# Soil_Moisture_V1_0.net
KiCad netlist of a schematic drawn in EAGLE
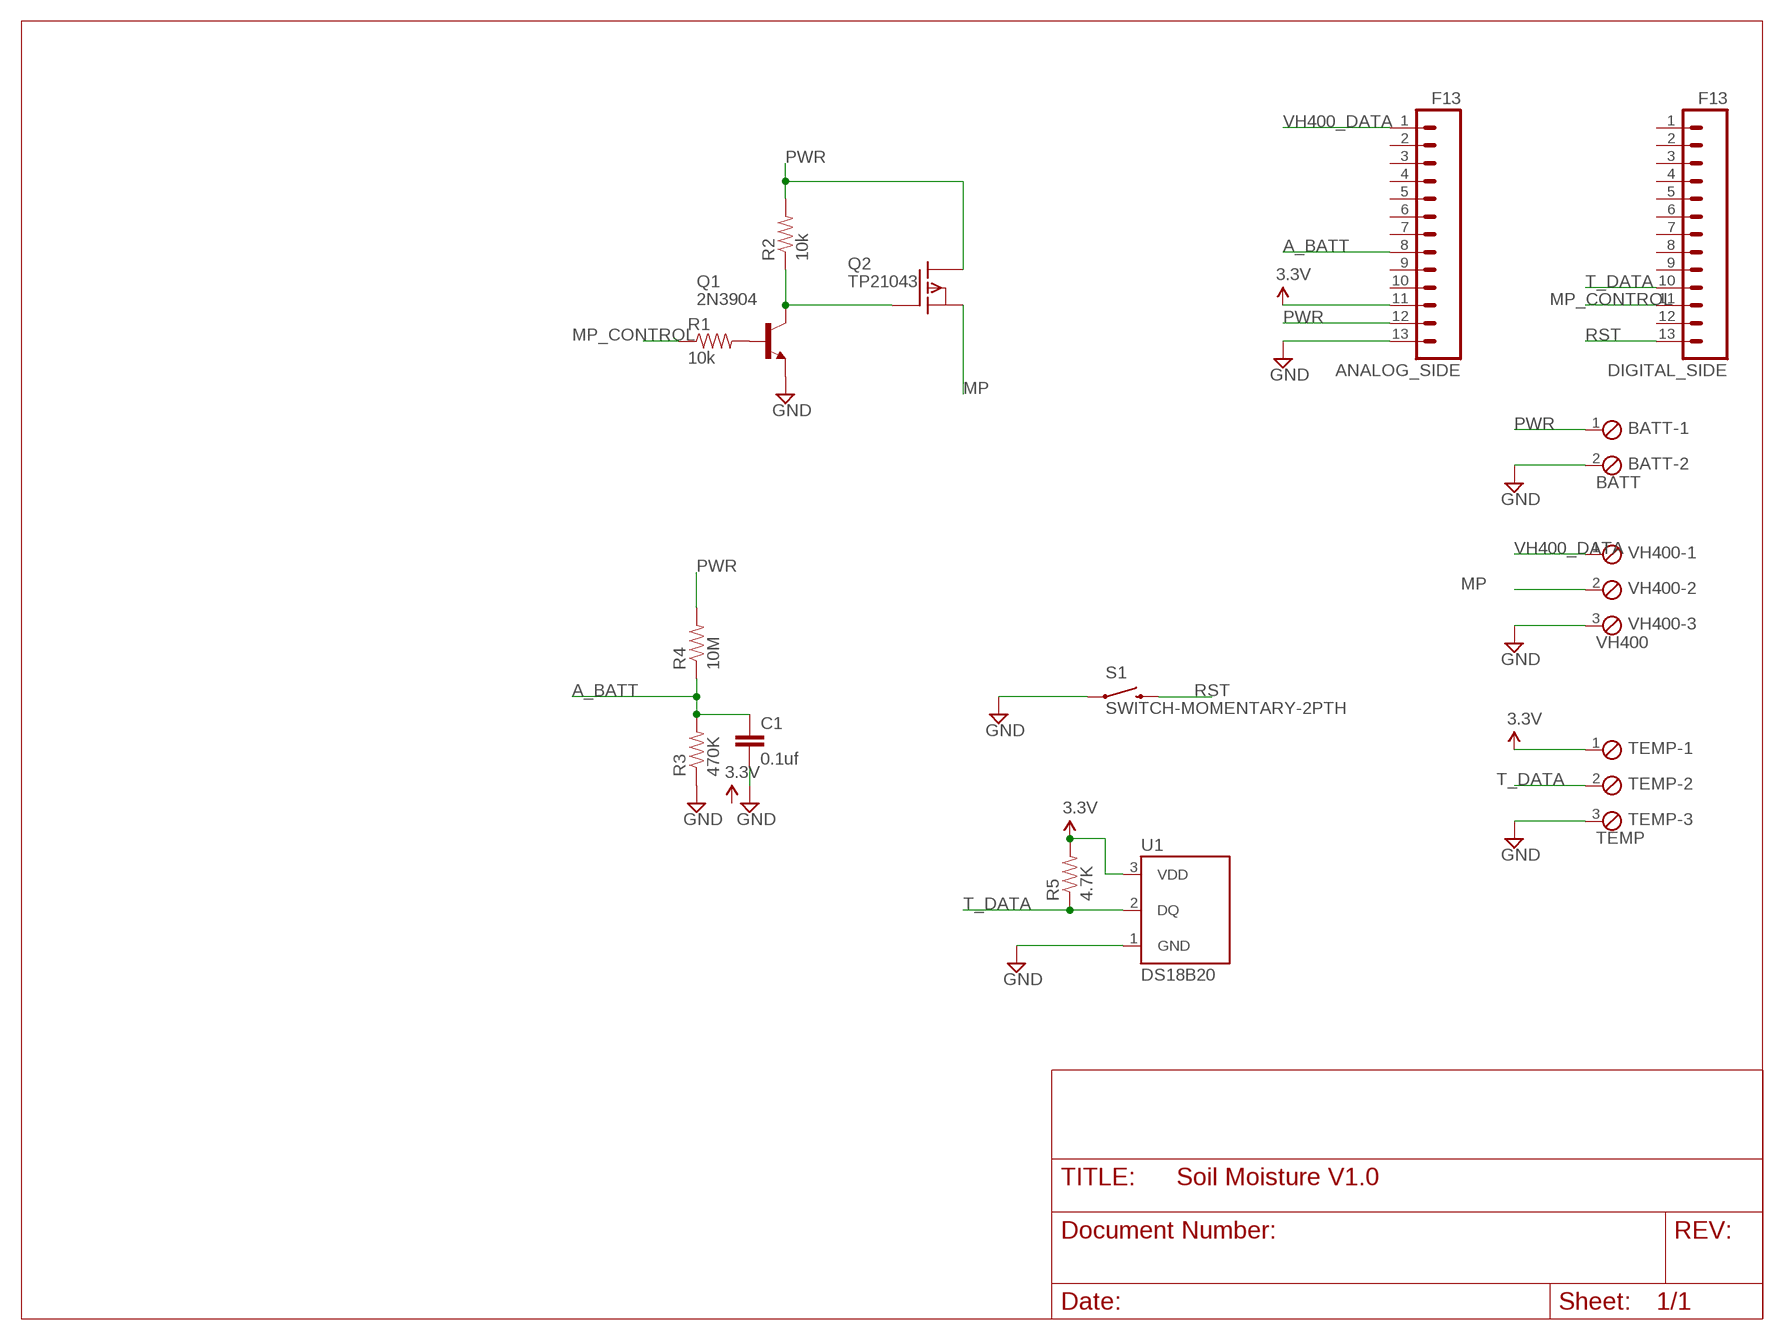
[diagram p0: schematic, sheet 1]

(export (version "E")
  (design (tool "Eeschema 10.0.6"))
  (components
    (comp (ref "ANALOG_SIDE")
      (value "F13")
      (footprint "eagle-import:1X13")
      (libsource (lib "eagle-import") (part "M13"))
    )
    (comp (ref "BATT")
      (value "BATT")
      (footprint "eagle-import:2POL254")
      (libsource (lib "eagle-import") (part "MPT2"))
    )
    (comp (ref "C1")
      (value "0.1uf")
      (footprint "eagle-import:CAP-PTH-SMALL-KIT")
      (libsource (lib "eagle-import") (part "0.1UF-50V-20%(PTH)KIT-EZ"))
    )
    (comp (ref "DIGITAL_SIDE")
      (value "F13")
      (footprint "eagle-import:1X13")
      (libsource (lib "eagle-import") (part "M13"))
    )
    (comp (ref "Q1")
      (value "2N3904")
      (footprint "eagle-import:TO92")
      (libsource (lib "eagle-import") (part "2N3904"))
    )
    (comp (ref "Q2")
      (value "TP21043")
      (footprint "eagle-import:TO92")
      (libsource (lib "eagle-import") (part "BSS110"))
    )
    (comp (ref "R1")
      (value "10k")
      (footprint "eagle-import:AXIAL-0.3EZ")
      (libsource (lib "eagle-import") (part "10KOHM-1/4W5%(PTH)HORIZ-KIT"))
    )
    (comp (ref "R2")
      (value "10k")
      (footprint "eagle-import:AXIAL-0.3EZ")
      (libsource (lib "eagle-import") (part "10KOHM-1/4W5%(PTH)HORIZ-KIT"))
    )
    (comp (ref "R3")
      (value "470K")
      (footprint "eagle-import:AXIAL-0.3")
      (libsource (lib "eagle-import") (part "10KOHM-1/4W-1%(PTH)HORIZ"))
    )
    (comp (ref "R4")
      (value "10M")
      (footprint "eagle-import:AXIAL-0.3")
      (libsource (lib "eagle-import") (part "10KOHM-1/4W-1%(PTH)HORIZ"))
    )
    (comp (ref "R5")
      (value "4.7K")
      (footprint "eagle-import:AXIAL-0.3")
      (libsource (lib "eagle-import") (part "10KOHM-1/4W5%(PTH)"))
    )
    (comp (ref "S1")
      (value "SWITCH-MOMENTARY-2PTH")
      (footprint "eagle-import:TACTILE-PTH")
      (libsource (lib "eagle-import") (part "SWITCH-MOMENTARY-2PTH"))
    )
    (comp (ref "TEMP")
      (value "TEMP")
      (footprint "eagle-import:3POL254")
      (libsource (lib "eagle-import") (part "MPT3"))
    )
    (comp (ref "U1")
      (value "DS18B20")
      (footprint "eagle-import:TO-92-AMMO")
      (libsource (lib "eagle-import") (part "DS18B20"))
    )
    (comp (ref "VH400")
      (value "VH400")
      (footprint "eagle-import:3POL254")
      (libsource (lib "eagle-import") (part "MPT3"))
    )
  )
  (nets
    (net (code "1") (name "/A_BATT") (class "Default")
      (node (ref "ANALOG_SIDE") (pin "8") (pinfunction "8_8") (pintype "passive"))
      (node (ref "C1") (pin "1") (pinfunction "1_1") (pintype "passive"))
      (node (ref "R3") (pin "P$2") (pinfunction "2_P$2") (pintype "passive"))
      (node (ref "R4") (pin "P$1") (pinfunction "1_P$1") (pintype "passive"))
    )
    (net (code "2") (name "/MP") (class "Default")
      (node (ref "Q2") (pin "1") (pinfunction "S_1") (pintype "passive"))
      (node (ref "VH400") (pin "2") (pinfunction "1_2") (pintype "passive"))
    )
    (net (code "3") (name "/MP_CONTROL") (class "Default")
      (node (ref "DIGITAL_SIDE") (pin "11") (pinfunction "11_11") (pintype "passive"))
      (node (ref "R1") (pin "P$1") (pinfunction "1_P$1") (pintype "passive"))
    )
    (net (code "4") (name "/PWR") (class "Default")
      (node (ref "ANALOG_SIDE") (pin "12") (pinfunction "12_12") (pintype "passive"))
      (node (ref "BATT") (pin "1") (pinfunction "1_1") (pintype "passive"))
      (node (ref "Q2") (pin "3") (pinfunction "D_3") (pintype "passive"))
      (node (ref "R2") (pin "P$2") (pinfunction "2_P$2") (pintype "passive"))
      (node (ref "R4") (pin "P$2") (pinfunction "2_P$2") (pintype "passive"))
    )
    (net (code "5") (name "/RST") (class "Default")
      (node (ref "DIGITAL_SIDE") (pin "13") (pinfunction "13_13") (pintype "passive"))
      (node (ref "S1") (pin "3") (pinfunction "2_3") (pintype "passive"))
    )
    (net (code "6") (name "/T_DATA") (class "Default")
      (node (ref "DIGITAL_SIDE") (pin "10") (pinfunction "10_10") (pintype "passive"))
      (node (ref "R5") (pin "P$1") (pinfunction "1_P$1") (pintype "passive"))
      (node (ref "TEMP") (pin "2") (pinfunction "1_2") (pintype "passive"))
      (node (ref "U1") (pin "2") (pinfunction "DQ_2") (pintype "bidirectional"))
    )
    (net (code "7") (name "/VH400_DATA") (class "Default")
      (node (ref "ANALOG_SIDE") (pin "1") (pinfunction "1_1") (pintype "passive"))
      (node (ref "VH400") (pin "1") (pinfunction "1_1") (pintype "passive"))
    )
    (net (code "8") (name "3.3V") (class "Default")
      (node (ref "ANALOG_SIDE") (pin "11") (pinfunction "11_11") (pintype "passive"))
      (node (ref "R5") (pin "P$2") (pinfunction "2_P$2") (pintype "passive"))
      (node (ref "TEMP") (pin "1") (pinfunction "1_1") (pintype "passive"))
      (node (ref "U1") (pin "3") (pinfunction "VDD_3") (pintype "power_in"))
    )
    (net (code "9") (name "GND") (class "Default")
      (node (ref "ANALOG_SIDE") (pin "13") (pinfunction "13_13") (pintype "passive"))
      (node (ref "BATT") (pin "2") (pinfunction "1_2") (pintype "passive"))
      (node (ref "C1") (pin "2") (pinfunction "2_2") (pintype "passive"))
      (node (ref "Q1") (pin "3") (pinfunction "E_3") (pintype "passive"))
      (node (ref "R3") (pin "P$1") (pinfunction "1_P$1") (pintype "passive"))
      (node (ref "S1") (pin "1") (pinfunction "1_1") (pintype "passive"))
      (node (ref "TEMP") (pin "3") (pinfunction "1_3") (pintype "passive"))
      (node (ref "U1") (pin "1") (pinfunction "GND_1") (pintype "power_in"))
      (node (ref "VH400") (pin "3") (pinfunction "1_3") (pintype "passive"))
    )
    (net (code "10") (name "Net-(Q1-B)") (class "Default")
      (node (ref "Q1") (pin "2") (pinfunction "B_2") (pintype "passive"))
      (node (ref "R1") (pin "P$2") (pinfunction "2_P$2") (pintype "passive"))
    )
    (net (code "11") (name "Net-(Q1-C)") (class "Default")
      (node (ref "Q1") (pin "1") (pinfunction "C_1") (pintype "passive"))
      (node (ref "Q2") (pin "2") (pinfunction "G_2") (pintype "passive"))
      (node (ref "R2") (pin "P$1") (pinfunction "1_P$1") (pintype "passive"))
    )
    (net (code "12") (name "unconnected-(ANALOG_SIDE-Pad2)") (class "Default")
      (node (ref "ANALOG_SIDE") (pin "2") (pinfunction "2_2") (pintype "passive"))
    )
    (net (code "13") (name "unconnected-(ANALOG_SIDE-Pad3)") (class "Default")
      (node (ref "ANALOG_SIDE") (pin "3") (pinfunction "3_3") (pintype "passive"))
    )
    (net (code "14") (name "unconnected-(ANALOG_SIDE-Pad4)") (class "Default")
      (node (ref "ANALOG_SIDE") (pin "4") (pinfunction "4_4") (pintype "passive"))
    )
    (net (code "15") (name "unconnected-(ANALOG_SIDE-Pad5)") (class "Default")
      (node (ref "ANALOG_SIDE") (pin "5") (pinfunction "5_5") (pintype "passive"))
    )
    (net (code "16") (name "unconnected-(ANALOG_SIDE-Pad6)") (class "Default")
      (node (ref "ANALOG_SIDE") (pin "6") (pinfunction "6_6") (pintype "passive"))
    )
    (net (code "17") (name "unconnected-(ANALOG_SIDE-Pad7)") (class "Default")
      (node (ref "ANALOG_SIDE") (pin "7") (pinfunction "7_7") (pintype "passive"))
    )
    (net (code "18") (name "unconnected-(ANALOG_SIDE-Pad9)") (class "Default")
      (node (ref "ANALOG_SIDE") (pin "9") (pinfunction "9_9") (pintype "passive"))
    )
    (net (code "19") (name "unconnected-(ANALOG_SIDE-Pad10)") (class "Default")
      (node (ref "ANALOG_SIDE") (pin "10") (pinfunction "10_10") (pintype "passive"))
    )
    (net (code "20") (name "unconnected-(DIGITAL_SIDE-Pad1)") (class "Default")
      (node (ref "DIGITAL_SIDE") (pin "1") (pinfunction "1_1") (pintype "passive"))
    )
    (net (code "21") (name "unconnected-(DIGITAL_SIDE-Pad2)") (class "Default")
      (node (ref "DIGITAL_SIDE") (pin "2") (pinfunction "2_2") (pintype "passive"))
    )
    (net (code "22") (name "unconnected-(DIGITAL_SIDE-Pad3)") (class "Default")
      (node (ref "DIGITAL_SIDE") (pin "3") (pinfunction "3_3") (pintype "passive"))
    )
    (net (code "23") (name "unconnected-(DIGITAL_SIDE-Pad4)") (class "Default")
      (node (ref "DIGITAL_SIDE") (pin "4") (pinfunction "4_4") (pintype "passive"))
    )
    (net (code "24") (name "unconnected-(DIGITAL_SIDE-Pad5)") (class "Default")
      (node (ref "DIGITAL_SIDE") (pin "5") (pinfunction "5_5") (pintype "passive"))
    )
    (net (code "25") (name "unconnected-(DIGITAL_SIDE-Pad6)") (class "Default")
      (node (ref "DIGITAL_SIDE") (pin "6") (pinfunction "6_6") (pintype "passive"))
    )
    (net (code "26") (name "unconnected-(DIGITAL_SIDE-Pad7)") (class "Default")
      (node (ref "DIGITAL_SIDE") (pin "7") (pinfunction "7_7") (pintype "passive"))
    )
    (net (code "27") (name "unconnected-(DIGITAL_SIDE-Pad8)") (class "Default")
      (node (ref "DIGITAL_SIDE") (pin "8") (pinfunction "8_8") (pintype "passive"))
    )
    (net (code "28") (name "unconnected-(DIGITAL_SIDE-Pad9)") (class "Default")
      (node (ref "DIGITAL_SIDE") (pin "9") (pinfunction "9_9") (pintype "passive"))
    )
    (net (code "29") (name "unconnected-(DIGITAL_SIDE-Pad12)") (class "Default")
      (node (ref "DIGITAL_SIDE") (pin "12") (pinfunction "12_12") (pintype "passive"))
    )
  )
)
